# CON_PCI_Express_X16_164PIN.net
KiCad netlist of a schematic drawn in Altium Designer
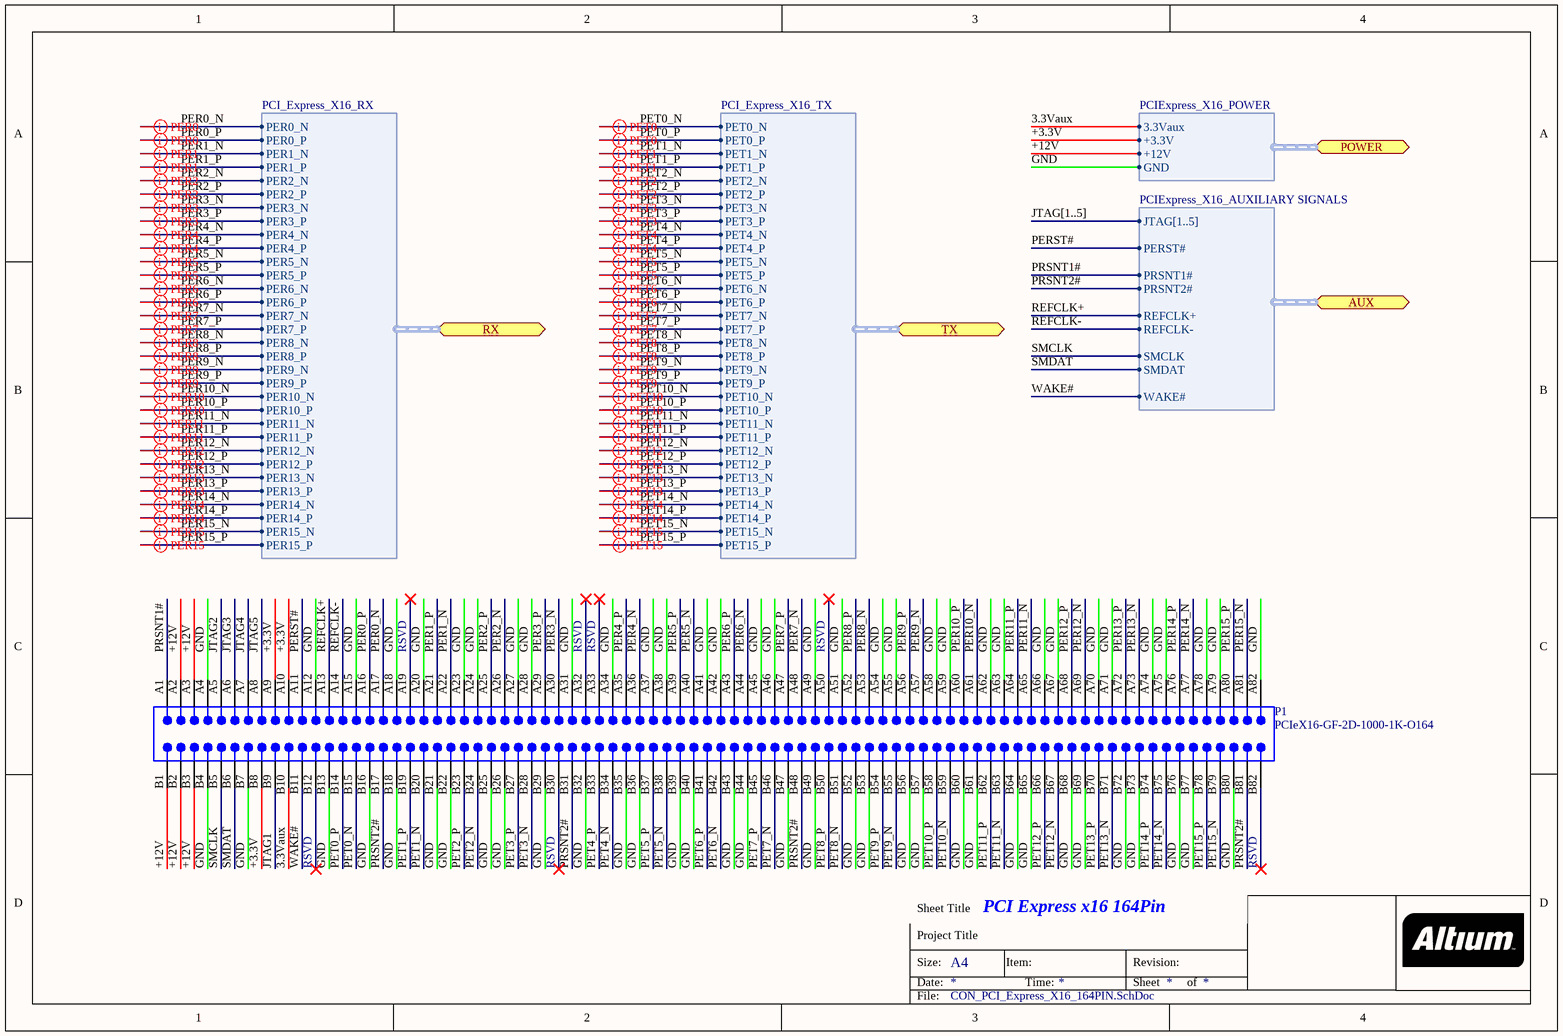
[diagram p0: CON_PCI_Express_X16_164PIN.SchDoc]

(export (version "E")
  (design (tool "Eeschema 10.0.6"))
  (components
    (comp (ref "P1")
      (value "PCIeX16-GF-2D-1000-1K-O164")
      (footprint "PCIeX16-GF-2D-1000-1K-O164")
      (description "Golden finger, PCIeX16, Dual, Opposite, Pitch 1mm, 164-Position")
      (fields (field (name "PUBLISHER") "Altium"))
      (libsource (lib "Altium Shanghai") (part "PCIeX16-GF-2D-1000-1K-O164"))
    )
  )
  (nets
    (net (code "7") (name "/+3.3V") (class "Default")
      (node (ref "P1") (pin "A10") (pinfunction "A10_A10") (pintype "passive"))
      (node (ref "P1") (pin "A9") (pinfunction "A9_A9") (pintype "passive"))
      (node (ref "P1") (pin "B8") (pinfunction "B8_B8") (pintype "passive"))
    )
    (net (code "8") (name "/+12V") (class "Default")
      (node (ref "P1") (pin "A2") (pinfunction "A2_A2") (pintype "passive"))
      (node (ref "P1") (pin "A3") (pinfunction "A3_A3") (pintype "passive"))
      (node (ref "P1") (pin "B1") (pinfunction "B1_B1") (pintype "passive"))
      (node (ref "P1") (pin "B2") (pinfunction "B2_B2") (pintype "passive"))
      (node (ref "P1") (pin "B3") (pinfunction "B3_B3") (pintype "passive"))
    )
    (net (code "9") (name "/3.3Vaux") (class "Default")
      (node (ref "P1") (pin "B10") (pinfunction "B10_B10") (pintype "passive"))
    )
    (net (code "11") (name "/GND") (class "Default")
      (node (ref "P1") (pin "A12") (pinfunction "A12_A12") (pintype "passive"))
      (node (ref "P1") (pin "A15") (pinfunction "A15_A15") (pintype "passive"))
      (node (ref "P1") (pin "A18") (pinfunction "A18_A18") (pintype "passive"))
      (node (ref "P1") (pin "A20") (pinfunction "A20_A20") (pintype "passive"))
      (node (ref "P1") (pin "A23") (pinfunction "A23_A23") (pintype "passive"))
      (node (ref "P1") (pin "A24") (pinfunction "A24_A24") (pintype "passive"))
      (node (ref "P1") (pin "A27") (pinfunction "A27_A27") (pintype "passive"))
      (node (ref "P1") (pin "A28") (pinfunction "A28_A28") (pintype "passive"))
      (node (ref "P1") (pin "A31") (pinfunction "A31_A31") (pintype "passive"))
      (node (ref "P1") (pin "A34") (pinfunction "A34_A34") (pintype "passive"))
      (node (ref "P1") (pin "A37") (pinfunction "A37_A37") (pintype "passive"))
      (node (ref "P1") (pin "A38") (pinfunction "A38_A38") (pintype "passive"))
      (node (ref "P1") (pin "A4") (pinfunction "A4_A4") (pintype "passive"))
      (node (ref "P1") (pin "A41") (pinfunction "A41_A41") (pintype "passive"))
      (node (ref "P1") (pin "A42") (pinfunction "A42_A42") (pintype "passive"))
      (node (ref "P1") (pin "A45") (pinfunction "A45_A45") (pintype "passive"))
      (node (ref "P1") (pin "A46") (pinfunction "A46_A46") (pintype "passive"))
      (node (ref "P1") (pin "A49") (pinfunction "A49_A49") (pintype "passive"))
      (node (ref "P1") (pin "A51") (pinfunction "A51_A51") (pintype "passive"))
      (node (ref "P1") (pin "A54") (pinfunction "A54_A54") (pintype "passive"))
      (node (ref "P1") (pin "A55") (pinfunction "A55_A55") (pintype "passive"))
      (node (ref "P1") (pin "A58") (pinfunction "A58_A58") (pintype "passive"))
      (node (ref "P1") (pin "A59") (pinfunction "A59_A59") (pintype "passive"))
      (node (ref "P1") (pin "A62") (pinfunction "A62_A62") (pintype "passive"))
      (node (ref "P1") (pin "A63") (pinfunction "A63_A63") (pintype "passive"))
      (node (ref "P1") (pin "A66") (pinfunction "A66_A66") (pintype "passive"))
      (node (ref "P1") (pin "A67") (pinfunction "A67_A67") (pintype "passive"))
      (node (ref "P1") (pin "A70") (pinfunction "A70_A70") (pintype "passive"))
      (node (ref "P1") (pin "A71") (pinfunction "A71_A71") (pintype "passive"))
      (node (ref "P1") (pin "A74") (pinfunction "A74_A74") (pintype "passive"))
      (node (ref "P1") (pin "A75") (pinfunction "A75_A75") (pintype "passive"))
      (node (ref "P1") (pin "A78") (pinfunction "A78_A78") (pintype "passive"))
      (node (ref "P1") (pin "A79") (pinfunction "A79_A79") (pintype "passive"))
      (node (ref "P1") (pin "A82") (pinfunction "A82_A82") (pintype "passive"))
      (node (ref "P1") (pin "B13") (pinfunction "B13_B13") (pintype "passive"))
      (node (ref "P1") (pin "B16") (pinfunction "B16_B16") (pintype "passive"))
      (node (ref "P1") (pin "B18") (pinfunction "B18_B18") (pintype "passive"))
      (node (ref "P1") (pin "B21") (pinfunction "B21_B21") (pintype "passive"))
      (node (ref "P1") (pin "B22") (pinfunction "B22_B22") (pintype "passive"))
      (node (ref "P1") (pin "B25") (pinfunction "B25_B25") (pintype "passive"))
      (node (ref "P1") (pin "B26") (pinfunction "B26_B26") (pintype "passive"))
      (node (ref "P1") (pin "B29") (pinfunction "B29_B29") (pintype "passive"))
      (node (ref "P1") (pin "B32") (pinfunction "B32_B32") (pintype "passive"))
      (node (ref "P1") (pin "B35") (pinfunction "B35_B35") (pintype "passive"))
      (node (ref "P1") (pin "B36") (pinfunction "B36_B36") (pintype "passive"))
      (node (ref "P1") (pin "B39") (pinfunction "B39_B39") (pintype "passive"))
      (node (ref "P1") (pin "B4") (pinfunction "B4_B4") (pintype "passive"))
      (node (ref "P1") (pin "B40") (pinfunction "B40_B40") (pintype "passive"))
      (node (ref "P1") (pin "B43") (pinfunction "B43_B43") (pintype "passive"))
      (node (ref "P1") (pin "B44") (pinfunction "B44_B44") (pintype "passive"))
      (node (ref "P1") (pin "B47") (pinfunction "B47_B47") (pintype "passive"))
      (node (ref "P1") (pin "B49") (pinfunction "B49_B49") (pintype "passive"))
      (node (ref "P1") (pin "B52") (pinfunction "B52_B52") (pintype "passive"))
      (node (ref "P1") (pin "B53") (pinfunction "B53_B53") (pintype "passive"))
      (node (ref "P1") (pin "B56") (pinfunction "B56_B56") (pintype "passive"))
      (node (ref "P1") (pin "B57") (pinfunction "B57_B57") (pintype "passive"))
      (node (ref "P1") (pin "B60") (pinfunction "B60_B60") (pintype "passive"))
      (node (ref "P1") (pin "B61") (pinfunction "B61_B61") (pintype "passive"))
      (node (ref "P1") (pin "B64") (pinfunction "B64_B64") (pintype "passive"))
      (node (ref "P1") (pin "B65") (pinfunction "B65_B65") (pintype "passive"))
      (node (ref "P1") (pin "B68") (pinfunction "B68_B68") (pintype "passive"))
      (node (ref "P1") (pin "B69") (pinfunction "B69_B69") (pintype "passive"))
      (node (ref "P1") (pin "B7") (pinfunction "B7_B7") (pintype "passive"))
      (node (ref "P1") (pin "B72") (pinfunction "B72_B72") (pintype "passive"))
      (node (ref "P1") (pin "B73") (pinfunction "B73_B73") (pintype "passive"))
      (node (ref "P1") (pin "B76") (pinfunction "B76_B76") (pintype "passive"))
      (node (ref "P1") (pin "B77") (pinfunction "B77_B77") (pintype "passive"))
      (node (ref "P1") (pin "B80") (pinfunction "B80_B80") (pintype "passive"))
    )
    (net (code "12") (name "/JTAG1") (class "Default")
      (node (ref "P1") (pin "B9") (pinfunction "B9_B9") (pintype "passive"))
    )
    (net (code "13") (name "/JTAG2") (class "Default")
      (node (ref "P1") (pin "A5") (pinfunction "A5_A5") (pintype "passive"))
    )
    (net (code "14") (name "/JTAG3") (class "Default")
      (node (ref "P1") (pin "A6") (pinfunction "A6_A6") (pintype "passive"))
    )
    (net (code "15") (name "/JTAG4") (class "Default")
      (node (ref "P1") (pin "A7") (pinfunction "A7_A7") (pintype "passive"))
    )
    (net (code "16") (name "/JTAG5") (class "Default")
      (node (ref "P1") (pin "A8") (pinfunction "A8_A8") (pintype "passive"))
    )
    (net (code "17") (name "/PER0_N") (class "Default")
      (node (ref "P1") (pin "A17") (pinfunction "A17_A17") (pintype "passive"))
    )
    (net (code "18") (name "/PER0_P") (class "Default")
      (node (ref "P1") (pin "A16") (pinfunction "A16_A16") (pintype "passive"))
    )
    (net (code "19") (name "/PER1_N") (class "Default")
      (node (ref "P1") (pin "A22") (pinfunction "A22_A22") (pintype "passive"))
    )
    (net (code "20") (name "/PER1_P") (class "Default")
      (node (ref "P1") (pin "A21") (pinfunction "A21_A21") (pintype "passive"))
    )
    (net (code "21") (name "/PER2_N") (class "Default")
      (node (ref "P1") (pin "A26") (pinfunction "A26_A26") (pintype "passive"))
    )
    (net (code "22") (name "/PER2_P") (class "Default")
      (node (ref "P1") (pin "A25") (pinfunction "A25_A25") (pintype "passive"))
    )
    (net (code "23") (name "/PER3_N") (class "Default")
      (node (ref "P1") (pin "A30") (pinfunction "A30_A30") (pintype "passive"))
    )
    (net (code "24") (name "/PER3_P") (class "Default")
      (node (ref "P1") (pin "A29") (pinfunction "A29_A29") (pintype "passive"))
    )
    (net (code "25") (name "/PER4_N") (class "Default")
      (node (ref "P1") (pin "A36") (pinfunction "A36_A36") (pintype "passive"))
    )
    (net (code "26") (name "/PER4_P") (class "Default")
      (node (ref "P1") (pin "A35") (pinfunction "A35_A35") (pintype "passive"))
    )
    (net (code "27") (name "/PER5_N") (class "Default")
      (node (ref "P1") (pin "A40") (pinfunction "A40_A40") (pintype "passive"))
    )
    (net (code "28") (name "/PER5_P") (class "Default")
      (node (ref "P1") (pin "A39") (pinfunction "A39_A39") (pintype "passive"))
    )
    (net (code "29") (name "/PER6_N") (class "Default")
      (node (ref "P1") (pin "A44") (pinfunction "A44_A44") (pintype "passive"))
    )
    (net (code "30") (name "/PER6_P") (class "Default")
      (node (ref "P1") (pin "A43") (pinfunction "A43_A43") (pintype "passive"))
    )
    (net (code "31") (name "/PER7_N") (class "Default")
      (node (ref "P1") (pin "A48") (pinfunction "A48_A48") (pintype "passive"))
    )
    (net (code "32") (name "/PER7_P") (class "Default")
      (node (ref "P1") (pin "A47") (pinfunction "A47_A47") (pintype "passive"))
    )
    (net (code "33") (name "/PER8_N") (class "Default")
      (node (ref "P1") (pin "A53") (pinfunction "A53_A53") (pintype "passive"))
    )
    (net (code "34") (name "/PER8_P") (class "Default")
      (node (ref "P1") (pin "A52") (pinfunction "A52_A52") (pintype "passive"))
    )
    (net (code "35") (name "/PER9_N") (class "Default")
      (node (ref "P1") (pin "A57") (pinfunction "A57_A57") (pintype "passive"))
    )
    (net (code "36") (name "/PER9_P") (class "Default")
      (node (ref "P1") (pin "A56") (pinfunction "A56_A56") (pintype "passive"))
    )
    (net (code "37") (name "/PER10_N") (class "Default")
      (node (ref "P1") (pin "A61") (pinfunction "A61_A61") (pintype "passive"))
    )
    (net (code "38") (name "/PER10_P") (class "Default")
      (node (ref "P1") (pin "A60") (pinfunction "A60_A60") (pintype "passive"))
    )
    (net (code "39") (name "/PER11_N") (class "Default")
      (node (ref "P1") (pin "A65") (pinfunction "A65_A65") (pintype "passive"))
    )
    (net (code "40") (name "/PER11_P") (class "Default")
      (node (ref "P1") (pin "A64") (pinfunction "A64_A64") (pintype "passive"))
    )
    (net (code "41") (name "/PER12_N") (class "Default")
      (node (ref "P1") (pin "A69") (pinfunction "A69_A69") (pintype "passive"))
    )
    (net (code "42") (name "/PER12_P") (class "Default")
      (node (ref "P1") (pin "A68") (pinfunction "A68_A68") (pintype "passive"))
    )
    (net (code "43") (name "/PER13_N") (class "Default")
      (node (ref "P1") (pin "A73") (pinfunction "A73_A73") (pintype "passive"))
    )
    (net (code "44") (name "/PER13_P") (class "Default")
      (node (ref "P1") (pin "A72") (pinfunction "A72_A72") (pintype "passive"))
    )
    (net (code "45") (name "/PER14_N") (class "Default")
      (node (ref "P1") (pin "A77") (pinfunction "A77_A77") (pintype "passive"))
    )
    (net (code "46") (name "/PER14_P") (class "Default")
      (node (ref "P1") (pin "A76") (pinfunction "A76_A76") (pintype "passive"))
    )
    (net (code "47") (name "/PER15_N") (class "Default")
      (node (ref "P1") (pin "A81") (pinfunction "A81_A81") (pintype "passive"))
    )
    (net (code "48") (name "/PER15_P") (class "Default")
      (node (ref "P1") (pin "A80") (pinfunction "A80_A80") (pintype "passive"))
    )
    (net (code "49") (name "/PERST#") (class "Default")
      (node (ref "P1") (pin "A11") (pinfunction "A11_A11") (pintype "passive"))
    )
    (net (code "50") (name "/PET0_N") (class "Default")
      (node (ref "P1") (pin "B15") (pinfunction "B15_B15") (pintype "passive"))
    )
    (net (code "51") (name "/PET0_P") (class "Default")
      (node (ref "P1") (pin "B14") (pinfunction "B14_B14") (pintype "passive"))
    )
    (net (code "52") (name "/PET1_N") (class "Default")
      (node (ref "P1") (pin "B20") (pinfunction "B20_B20") (pintype "passive"))
    )
    (net (code "53") (name "/PET1_P") (class "Default")
      (node (ref "P1") (pin "B19") (pinfunction "B19_B19") (pintype "passive"))
    )
    (net (code "54") (name "/PET2_N") (class "Default")
      (node (ref "P1") (pin "B24") (pinfunction "B24_B24") (pintype "passive"))
    )
    (net (code "55") (name "/PET2_P") (class "Default")
      (node (ref "P1") (pin "B23") (pinfunction "B23_B23") (pintype "passive"))
    )
    (net (code "56") (name "/PET3_N") (class "Default")
      (node (ref "P1") (pin "B28") (pinfunction "B28_B28") (pintype "passive"))
    )
    (net (code "57") (name "/PET3_P") (class "Default")
      (node (ref "P1") (pin "B27") (pinfunction "B27_B27") (pintype "passive"))
    )
    (net (code "58") (name "/PET4_N") (class "Default")
      (node (ref "P1") (pin "B34") (pinfunction "B34_B34") (pintype "passive"))
    )
    (net (code "59") (name "/PET4_P") (class "Default")
      (node (ref "P1") (pin "B33") (pinfunction "B33_B33") (pintype "passive"))
    )
    (net (code "60") (name "/PET5_N") (class "Default")
      (node (ref "P1") (pin "B38") (pinfunction "B38_B38") (pintype "passive"))
    )
    (net (code "61") (name "/PET5_P") (class "Default")
      (node (ref "P1") (pin "B37") (pinfunction "B37_B37") (pintype "passive"))
    )
    (net (code "62") (name "/PET6_N") (class "Default")
      (node (ref "P1") (pin "B42") (pinfunction "B42_B42") (pintype "passive"))
    )
    (net (code "63") (name "/PET6_P") (class "Default")
      (node (ref "P1") (pin "B41") (pinfunction "B41_B41") (pintype "passive"))
    )
    (net (code "64") (name "/PET7_N") (class "Default")
      (node (ref "P1") (pin "B46") (pinfunction "B46_B46") (pintype "passive"))
    )
    (net (code "65") (name "/PET7_P") (class "Default")
      (node (ref "P1") (pin "B45") (pinfunction "B45_B45") (pintype "passive"))
    )
    (net (code "66") (name "/PET8_N") (class "Default")
      (node (ref "P1") (pin "B51") (pinfunction "B51_B51") (pintype "passive"))
    )
    (net (code "67") (name "/PET8_P") (class "Default")
      (node (ref "P1") (pin "B50") (pinfunction "B50_B50") (pintype "passive"))
    )
    (net (code "68") (name "/PET9_N") (class "Default")
      (node (ref "P1") (pin "B55") (pinfunction "B55_B55") (pintype "passive"))
    )
    (net (code "69") (name "/PET9_P") (class "Default")
      (node (ref "P1") (pin "B54") (pinfunction "B54_B54") (pintype "passive"))
    )
    (net (code "70") (name "/PET10_N") (class "Default")
      (node (ref "P1") (pin "B59") (pinfunction "B59_B59") (pintype "passive"))
    )
    (net (code "71") (name "/PET10_P") (class "Default")
      (node (ref "P1") (pin "B58") (pinfunction "B58_B58") (pintype "passive"))
    )
    (net (code "72") (name "/PET11_N") (class "Default")
      (node (ref "P1") (pin "B63") (pinfunction "B63_B63") (pintype "passive"))
    )
    (net (code "73") (name "/PET11_P") (class "Default")
      (node (ref "P1") (pin "B62") (pinfunction "B62_B62") (pintype "passive"))
    )
    (net (code "74") (name "/PET12_N") (class "Default")
      (node (ref "P1") (pin "B67") (pinfunction "B67_B67") (pintype "passive"))
    )
    (net (code "75") (name "/PET12_P") (class "Default")
      (node (ref "P1") (pin "B66") (pinfunction "B66_B66") (pintype "passive"))
    )
    (net (code "76") (name "/PET13_N") (class "Default")
      (node (ref "P1") (pin "B71") (pinfunction "B71_B71") (pintype "passive"))
    )
    (net (code "77") (name "/PET13_P") (class "Default")
      (node (ref "P1") (pin "B70") (pinfunction "B70_B70") (pintype "passive"))
    )
    (net (code "78") (name "/PET14_N") (class "Default")
      (node (ref "P1") (pin "B75") (pinfunction "B75_B75") (pintype "passive"))
    )
    (net (code "79") (name "/PET14_P") (class "Default")
      (node (ref "P1") (pin "B74") (pinfunction "B74_B74") (pintype "passive"))
    )
    (net (code "80") (name "/PET15_N") (class "Default")
      (node (ref "P1") (pin "B79") (pinfunction "B79_B79") (pintype "passive"))
    )
    (net (code "81") (name "/PET15_P") (class "Default")
      (node (ref "P1") (pin "B78") (pinfunction "B78_B78") (pintype "passive"))
    )
    (net (code "82") (name "/PRSNT1#") (class "Default")
      (node (ref "P1") (pin "A1") (pinfunction "A1_A1") (pintype "passive"))
    )
    (net (code "83") (name "/PRSNT2#") (class "Default")
      (node (ref "P1") (pin "B17") (pinfunction "B17_B17") (pintype "passive"))
      (node (ref "P1") (pin "B31") (pinfunction "B31_B31") (pintype "passive"))
      (node (ref "P1") (pin "B48") (pinfunction "B48_B48") (pintype "passive"))
      (node (ref "P1") (pin "B81") (pinfunction "B81_B81") (pintype "passive"))
    )
    (net (code "84") (name "/REFCLK+") (class "Default")
      (node (ref "P1") (pin "A13") (pinfunction "A13_A13") (pintype "passive"))
    )
    (net (code "85") (name "/REFCLK-") (class "Default")
      (node (ref "P1") (pin "A14") (pinfunction "A14_A14") (pintype "passive"))
    )
    (net (code "86") (name "/SMCLK") (class "Default")
      (node (ref "P1") (pin "B5") (pinfunction "B5_B5") (pintype "passive"))
    )
    (net (code "87") (name "/SMDAT") (class "Default")
      (node (ref "P1") (pin "B6") (pinfunction "B6_B6") (pintype "passive"))
    )
    (net (code "88") (name "/WAKE#") (class "Default")
      (node (ref "P1") (pin "B11") (pinfunction "B11_B11") (pintype "passive"))
    )
    (net (code "93") (name "unconnected-(P1-PadA19)") (class "Default")
      (node (ref "P1") (pin "A19") (pinfunction "A19_A19") (pintype "passive+no_connect"))
    )
    (net (code "94") (name "unconnected-(P1-PadA32)") (class "Default")
      (node (ref "P1") (pin "A32") (pinfunction "A32_A32") (pintype "passive+no_connect"))
    )
    (net (code "95") (name "unconnected-(P1-PadA33)") (class "Default")
      (node (ref "P1") (pin "A33") (pinfunction "A33_A33") (pintype "passive+no_connect"))
    )
    (net (code "96") (name "unconnected-(P1-PadA50)") (class "Default")
      (node (ref "P1") (pin "A50") (pinfunction "A50_A50") (pintype "passive+no_connect"))
    )
    (net (code "97") (name "unconnected-(P1-PadB12)") (class "Default")
      (node (ref "P1") (pin "B12") (pinfunction "B12_B12") (pintype "passive+no_connect"))
    )
    (net (code "98") (name "unconnected-(P1-PadB30)") (class "Default")
      (node (ref "P1") (pin "B30") (pinfunction "B30_B30") (pintype "passive+no_connect"))
    )
    (net (code "99") (name "unconnected-(P1-PadB82)") (class "Default")
      (node (ref "P1") (pin "B82") (pinfunction "B82_B82") (pintype "passive+no_connect"))
    )
  )
)
